# Sch.net
KiCad netlist of a schematic drawn in Altium Designer
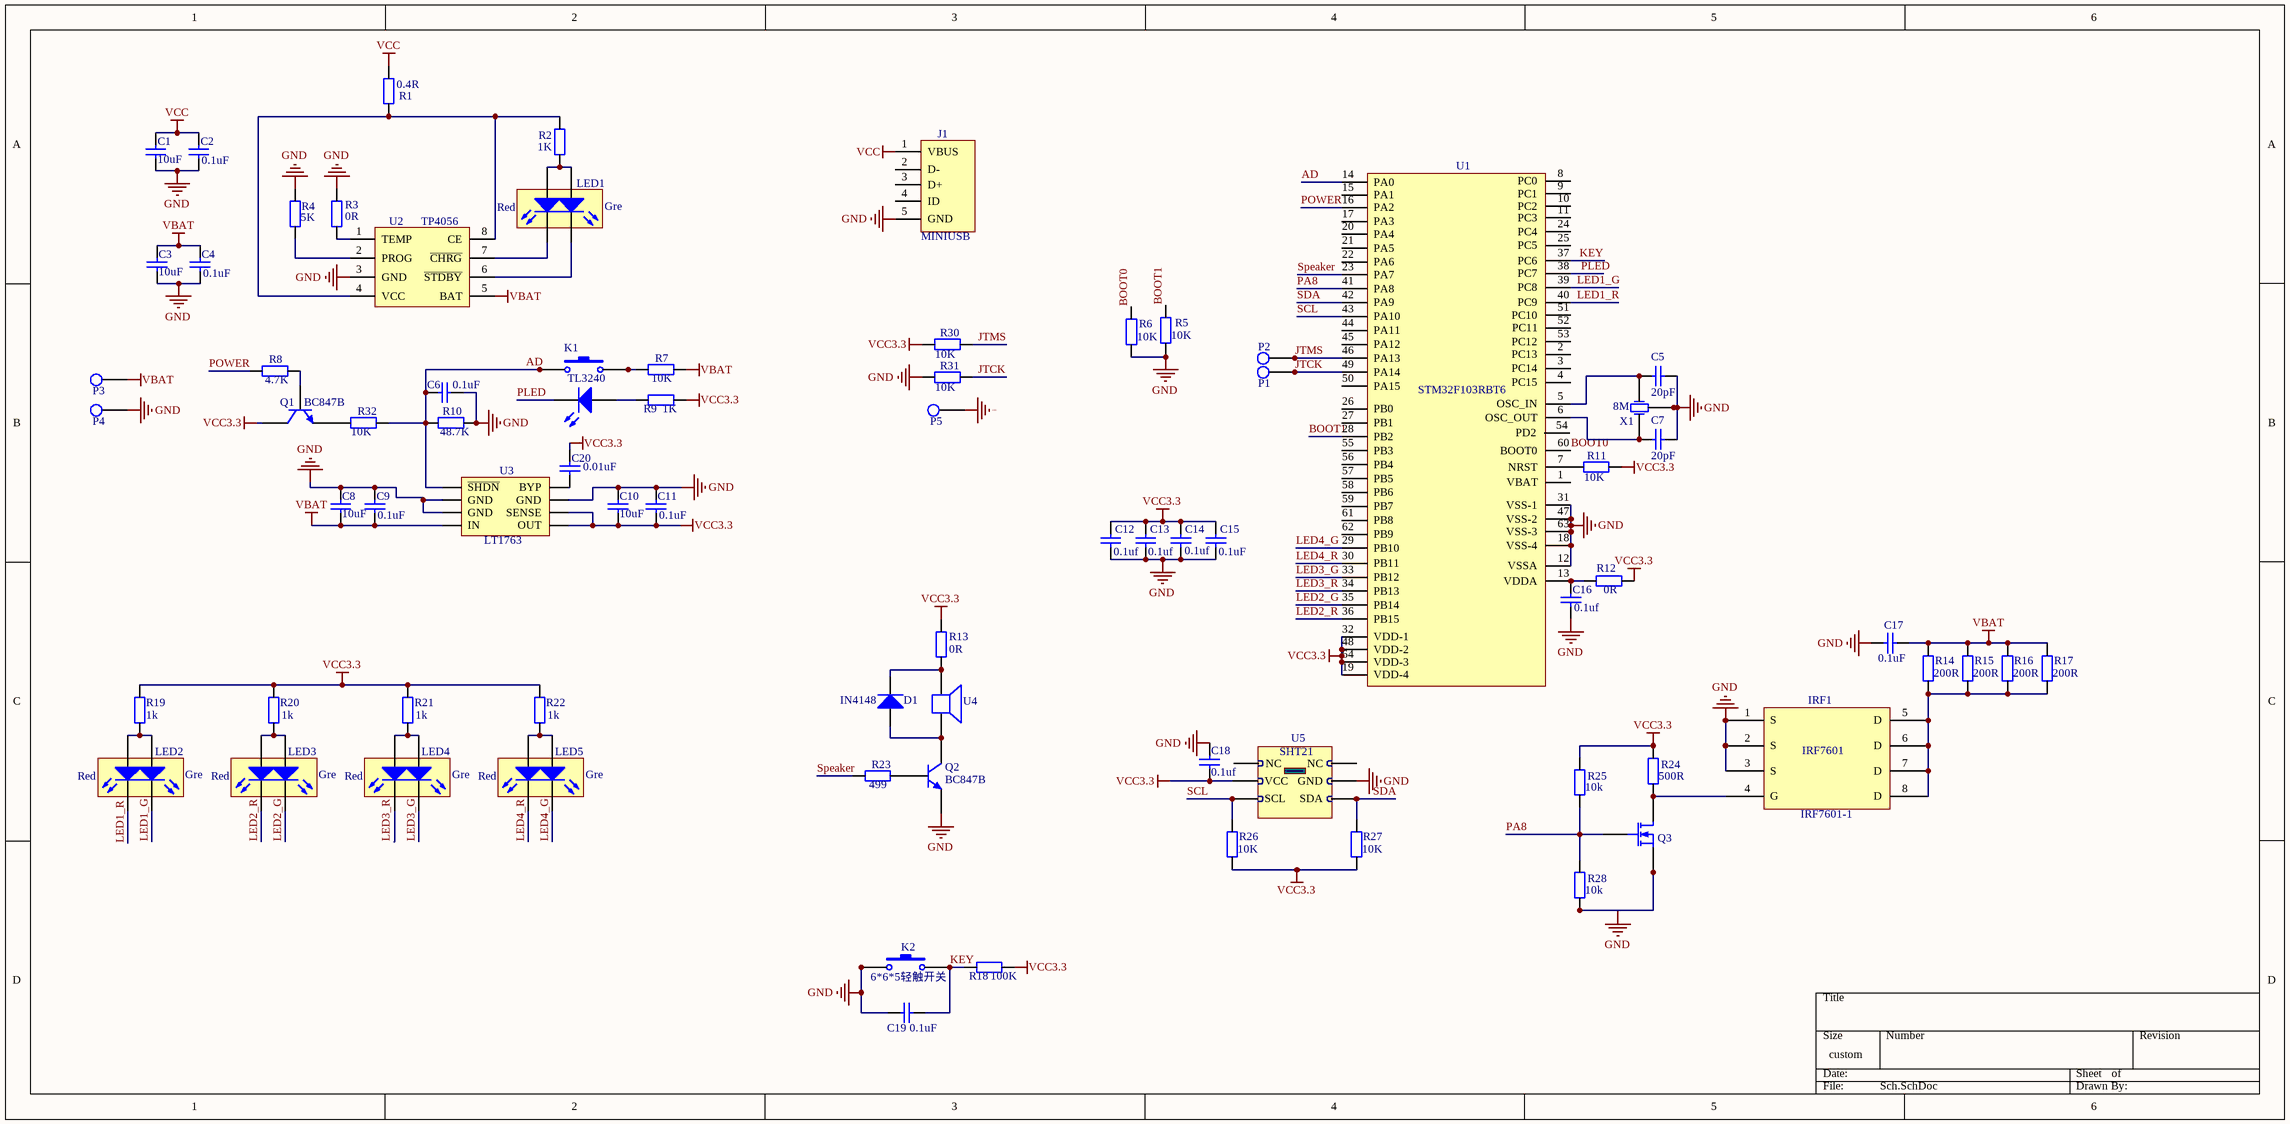
[diagram p0: Sch.SchDoc]

(export (version "E")
  (design (tool "Eeschema 10.0.6"))
  (components
    (comp (ref "C1")
      (value "10uF")
      (footprint "0805")
      (fields (field (name "Comment") "Capacitor-0805"))
      (libsource (lib "原理图库") (part "Capacitor-0805"))
    )
    (comp (ref "C2")
      (value "0.1uF")
      (footprint "0603")
      (fields (field (name "Comment") "Capacitor-0603"))
      (libsource (lib "原理图库") (part "Capacitor-0603"))
    )
    (comp (ref "C3")
      (value "10uF")
      (footprint "0805")
      (fields (field (name "Comment") "Capacitor-0805"))
      (libsource (lib "原理图库") (part "Capacitor-0805"))
    )
    (comp (ref "C4")
      (value "0.1uF")
      (footprint "0603")
      (fields (field (name "Comment") "Capacitor-0603"))
      (libsource (lib "原理图库") (part "Capacitor-0603"))
    )
    (comp (ref "C5")
      (value "20pF")
      (footprint "0603")
      (fields (field (name "Comment") "Capacitor-0805"))
      (libsource (lib "原理图库") (part "Capacitor-0805"))
    )
    (comp (ref "C6")
      (value "0.1uF")
      (footprint "0603")
      (fields (field (name "Comment") "Capacitor-0603"))
      (libsource (lib "原理图库") (part "Capacitor-0603"))
    )
    (comp (ref "C7")
      (value "20pF")
      (footprint "0603")
      (fields (field (name "Comment") "Capacitor-0805"))
      (libsource (lib "原理图库") (part "Capacitor-0805"))
    )
    (comp (ref "C8")
      (value "10uF")
      (footprint "0805")
      (fields (field (name "Comment") "Capacitor-0805"))
      (libsource (lib "原理图库") (part "Capacitor-0805"))
    )
    (comp (ref "C9")
      (value "0.1uF")
      (footprint "0603")
      (fields (field (name "Comment") "Capacitor-0603"))
      (libsource (lib "原理图库") (part "Capacitor-0603"))
    )
    (comp (ref "C10")
      (value "10uF")
      (footprint "0805")
      (fields (field (name "Comment") "Capacitor-0805"))
      (libsource (lib "原理图库") (part "Capacitor-0805"))
    )
    (comp (ref "C11")
      (value "0.1uF")
      (footprint "0603")
      (fields (field (name "Comment") "Capacitor-0603"))
      (libsource (lib "原理图库") (part "Capacitor-0603"))
    )
    (comp (ref "C12")
      (value "0.1uf")
      (footprint "0603")
      (fields (field (name "Comment") "Capacitor-0603"))
      (libsource (lib "原理图库") (part "Capacitor-0603"))
    )
    (comp (ref "C13")
      (value "0.1uf")
      (footprint "0603")
      (fields (field (name "Comment") "Capacitor-0603"))
      (libsource (lib "原理图库") (part "Capacitor-0603"))
    )
    (comp (ref "C14")
      (value "0.1uf")
      (footprint "0603")
      (fields (field (name "Comment") "Capacitor-0603"))
      (libsource (lib "原理图库") (part "Capacitor-0603"))
    )
    (comp (ref "C15")
      (value "0.1uF")
      (footprint "0603")
      (fields (field (name "Comment") "Capacitor-0603"))
      (libsource (lib "原理图库") (part "Capacitor-0603"))
    )
    (comp (ref "C16")
      (value "0.1uf")
      (footprint "0603")
      (fields (field (name "Comment") "Capacitor-0603"))
      (libsource (lib "原理图库") (part "Capacitor-0603"))
    )
    (comp (ref "C17")
      (value "0.1uF")
      (footprint "0603")
      (fields (field (name "Comment") "Capacitor-0603"))
      (libsource (lib "原理图库") (part "Capacitor-0603"))
    )
    (comp (ref "C18")
      (value "0.1uf")
      (footprint "0603")
      (fields (field (name "Comment") "Capacitor-0603"))
      (libsource (lib "原理图库") (part "Capacitor-0603"))
    )
    (comp (ref "C19")
      (value "0.1uF")
      (footprint "0603")
      (fields (field (name "Comment") "Capacitor-0603"))
      (libsource (lib "原理图库") (part "Capacitor-0603"))
    )
    (comp (ref "C20")
      (value "0.01uF")
      (footprint "0603")
      (fields (field (name "Comment") "Capacitor-0805"))
      (libsource (lib "集成库—大岐") (part "Capacitor-0805"))
    )
    (comp (ref "D1")
      (value "IN5824")
      (footprint "IN5824")
      (fields (field (name "ALTIUM_UNNAMED_1") "IN4148"))
      (libsource (lib "集成库—大岐") (part "IN5824"))
    )
    (comp (ref "IRF1")
      (value "IRF7601-1")
      (footprint "IRF7601_Micro")
      (description "IRF7601")
      (libsource (lib "*") (part "Component_1"))
    )
    (comp (ref "J1")
      (value "MINIUSB")
      (footprint "MicoUsb")
      (fields (field (name "NAME") "MINIUSB"))
      (libsource (lib "原理图库") (part "MINIUSB"))
    )
    (comp (ref "K1") (value "TL3240") (footprint "TL3240") (libsource (lib "原理图库") (part "TL3240")))
    (comp (ref "K2")
      (value "6*6*5轻触开关")
      (footprint "四脚轻触开关（6*6*5）")
      (fields (field (name "Comment") "轻触开关"))
      (libsource (lib "原理图库") (part "轻触开关"))
    )
    (comp (ref "LED1")
      (value "LED0603*2")
      (footprint "LED0603*2")
      (libsource (lib "原理图库") (part "LED0603*2"))
    )
    (comp (ref "LED2")
      (value "LED0603*2")
      (footprint "LED0603*2")
      (libsource (lib "原理图库") (part "LED0603*2"))
    )
    (comp (ref "LED3")
      (value "LED0603*2")
      (footprint "LED0603*2")
      (libsource (lib "原理图库") (part "LED0603*2"))
    )
    (comp (ref "LED4")
      (value "LED0603*2")
      (footprint "LED0603*2")
      (libsource (lib "原理图库") (part "LED0603*2"))
    )
    (comp (ref "LED5")
      (value "LED0603*2")
      (footprint "LED0603*2")
      (libsource (lib "原理图库") (part "LED0603*2"))
    )
    (comp (ref "P1") (value "焊盘") (footprint "测点") (libsource (lib "原理图库") (part "焊盘")))
    (comp (ref "P2") (value "焊盘") (footprint "测点") (libsource (lib "原理图库") (part "焊盘")))
    (comp (ref "P3") (value "焊盘") (footprint "测点") (libsource (lib "原理图库") (part "焊盘")))
    (comp (ref "P4") (value "焊盘") (footprint "测点") (libsource (lib "原理图库") (part "焊盘")))
    (comp (ref "P5") (value "焊盘") (footprint "测点") (libsource (lib "原理图库") (part "焊盘")))
    (comp (ref "Q1")
      (value "BC847")
      (footprint "BC847B")
      (fields (field (name "NAME") "BC847B"))
      (libsource (lib "原理图库") (part "BC847"))
    )
    (comp (ref "Q2")
      (value "BC847")
      (footprint "BC847B")
      (fields (field (name "NAME") "BC847B"))
      (libsource (lib "原理图库") (part "BC847"))
    )
    (comp (ref "Q3") (value "MOSFET_N") (footprint "MOSFET_N") (libsource (lib "原理图库") (part "MOSFET_N")))
    (comp (ref "R1")
      (value "0.4R")
      (footprint "0603")
      (fields (field (name "Comment") "Resistor-0603"))
      (libsource (lib "原理图库") (part "Resistor-0603"))
    )
    (comp (ref "R2")
      (value "1K")
      (footprint "0603")
      (fields (field (name "Comment") "Resistor-0603"))
      (libsource (lib "") (part "Resistor-0603_3"))
    )
    (comp (ref "R3")
      (value "0R")
      (footprint "0603")
      (fields (field (name "Comment") "Resistor-0603"))
      (libsource (lib "") (part "Resistor-0603_3"))
    )
    (comp (ref "R4")
      (value "5K")
      (footprint "0603")
      (fields (field (name "Comment") "Resistor-0603"))
      (libsource (lib "") (part "Resistor-0603_3"))
    )
    (comp (ref "R5")
      (value "10K")
      (footprint "0603")
      (fields (field (name "Comment") "Resistor-0603"))
      (libsource (lib "原理图库") (part "Resistor-0603"))
    )
    (comp (ref "R6")
      (value "10K")
      (footprint "0603")
      (fields (field (name "Comment") "Resistor-0603"))
      (libsource (lib "原理图库") (part "Resistor-0603"))
    )
    (comp (ref "R7")
      (value "10K")
      (footprint "0603")
      (fields (field (name "Comment") "Resistor-0603"))
      (libsource (lib "") (part "Resistor-0603_2"))
    )
    (comp (ref "R8")
      (value "4.7K")
      (footprint "0603")
      (fields (field (name "Comment") "Resistor-0603"))
      (libsource (lib "") (part "Resistor-0603_1"))
    )
    (comp (ref "R9")
      (value "1K")
      (footprint "0603")
      (fields (field (name "Comment") "Resistor-0603"))
      (libsource (lib "") (part "Resistor-0603_2"))
    )
    (comp (ref "R10")
      (value "48.7K")
      (footprint "0603")
      (fields (field (name "Comment") "Resistor-0603"))
      (libsource (lib "") (part "Resistor-0603_2"))
    )
    (comp (ref "R11")
      (value "10K")
      (footprint "0603")
      (fields (field (name "Comment") "Resistor-0603"))
      (libsource (lib "") (part "Resistor-0603_1"))
    )
    (comp (ref "R12")
      (value "0R")
      (footprint "0603")
      (fields (field (name "Comment") "Resistor-0603"))
      (libsource (lib "") (part "Resistor-0603_1"))
    )
    (comp (ref "R13")
      (value "0R")
      (footprint "0603")
      (fields (field (name "Comment") "Resistor-0603"))
      (libsource (lib "原理图库") (part "Resistor-0603"))
    )
    (comp (ref "R14")
      (value "200R")
      (footprint "0805")
      (fields (field (name "Comment") "Resistor-0805"))
      (libsource (lib "原理图库") (part "Resistor-0805"))
    )
    (comp (ref "R15")
      (value "200R")
      (footprint "0805")
      (fields (field (name "Comment") "Resistor-0805"))
      (libsource (lib "原理图库") (part "Resistor-0805"))
    )
    (comp (ref "R16")
      (value "200R")
      (footprint "0805")
      (fields (field (name "Comment") "Resistor-0805"))
      (libsource (lib "原理图库") (part "Resistor-0805"))
    )
    (comp (ref "R17")
      (value "200R")
      (footprint "0805")
      (fields (field (name "Comment") "Resistor-0805"))
      (libsource (lib "原理图库") (part "Resistor-0805"))
    )
    (comp (ref "R18")
      (value "100K")
      (footprint "0603")
      (fields (field (name "Comment") "Resistor-0603"))
      (libsource (lib "") (part "Resistor-0603_2"))
    )
    (comp (ref "R19")
      (value "1k")
      (footprint "0603")
      (fields (field (name "Comment") "Resistor-0603"))
      (libsource (lib "原理图库") (part "Resistor-0603"))
    )
    (comp (ref "R20")
      (value "1k")
      (footprint "0603")
      (fields (field (name "Comment") "Resistor-0603"))
      (libsource (lib "原理图库") (part "Resistor-0603"))
    )
    (comp (ref "R21")
      (value "1k")
      (footprint "0603")
      (fields (field (name "Comment") "Resistor-0603"))
      (libsource (lib "原理图库") (part "Resistor-0603"))
    )
    (comp (ref "R22")
      (value "1k")
      (footprint "0603")
      (fields (field (name "Comment") "Resistor-0603"))
      (libsource (lib "原理图库") (part "Resistor-0603"))
    )
    (comp (ref "R23")
      (value "499")
      (footprint "0603")
      (fields (field (name "Comment") "Resistor-0603"))
      (libsource (lib "") (part "Resistor-0603_1"))
    )
    (comp (ref "R24")
      (value "500R")
      (footprint "0603")
      (fields (field (name "Comment") "Resistor-0603"))
      (libsource (lib "原理图库") (part "Resistor-0603"))
    )
    (comp (ref "R25")
      (value "10k")
      (footprint "0603")
      (fields (field (name "Comment") "Resistor-0603"))
      (libsource (lib "原理图库") (part "Resistor-0603"))
    )
    (comp (ref "R26")
      (value "10K")
      (footprint "0603")
      (fields (field (name "Comment") "Resistor-0603"))
      (libsource (lib "原理图库") (part "Resistor-0603"))
    )
    (comp (ref "R27")
      (value "10K")
      (footprint "0603")
      (fields (field (name "Comment") "Resistor-0603"))
      (libsource (lib "原理图库") (part "Resistor-0603"))
    )
    (comp (ref "R28")
      (value "10k")
      (footprint "0603")
      (fields (field (name "Comment") "Resistor-0603"))
      (libsource (lib "原理图库") (part "Resistor-0603"))
    )
    (comp (ref "R30")
      (value "10K")
      (footprint "0603")
      (fields (field (name "Comment") "Resistor-0603"))
      (libsource (lib "") (part "Resistor-0603_1"))
    )
    (comp (ref "R31")
      (value "10K")
      (footprint "0603")
      (fields (field (name "Comment") "Resistor-0603"))
      (libsource (lib "") (part "Resistor-0603_1"))
    )
    (comp (ref "R32")
      (value "10K")
      (footprint "0603")
      (fields (field (name "Comment") "Resistor-0603"))
      (libsource (lib "") (part "Resistor-0603_1"))
    )
    (comp (ref "U1")
      (value "STM32F103RBT6")
      (footprint "STM32F103RBT6")
      (fields (field (name "NAME") "STM32F103RBT6"))
      (libsource (lib "原理图库") (part "STM32F103RBT6"))
    )
    (comp (ref "U2") (value "TP4056") (footprint "TP4056") (libsource (lib "原理图库") (part "TP4056")))
    (comp (ref "U3") (value "LT1763") (footprint "LT1963") (libsource (lib "原理图库") (part "LT1763")))
    (comp (ref "U4")
      (value "Speaker")
      (footprint "Speaker（5*5*2.0）")
      (libsource (lib "原理图库") (part "Speaker"))
    )
    (comp (ref "U5")
      (value "SHIT21")
      (footprint "SHT21")
      (fields (field (name "NAME") "SHT21"))
      (libsource (lib "原理图库") (part "SHIT21"))
    )
    (comp (ref "X1")
      (value "8M")
      (footprint "3225无源晶振")
      (fields (field (name "Comment") "3225无源晶振"))
      (libsource (lib "原理图库") (part "3225无源晶振"))
    )
  )
  (nets
    (net (code "1") (name "/AD") (class "Default")
      (node (ref "C6") (pin "2") (pinfunction "2_2") (pintype "passive"))
      (node (ref "K1") (pin "1") (pinfunction "1_1") (pintype "passive"))
      (node (ref "K1") (pin "2") (pinfunction "2_2") (pintype "passive"))
      (node (ref "R10") (pin "1") (pinfunction "1_1") (pintype "passive"))
      (node (ref "R32") (pin "1") (pinfunction "1_1") (pintype "passive"))
      (node (ref "U1") (pin "14") (pinfunction "PA0_14") (pintype "passive"))
      (node (ref "U3") (pin "5") (pinfunction "~{SHDN}_5") (pintype "passive"))
    )
    (net (code "2") (name "/BOOT0") (class "Default")
      (node (ref "R6") (pin "2") (pinfunction "2_2") (pintype "passive"))
      (node (ref "U1") (pin "60") (pinfunction "BOOT0_60") (pintype "passive"))
    )
    (net (code "3") (name "/BOOT1") (class "Default")
      (node (ref "R5") (pin "2") (pinfunction "2_2") (pintype "passive"))
      (node (ref "U1") (pin "28") (pinfunction "PB2_28") (pintype "passive"))
    )
    (net (code "4") (name "/JTCK") (class "Default")
      (node (ref "P1") (pin "1") (pinfunction "1_1") (pintype "passive"))
      (node (ref "R31") (pin "1") (pinfunction "1_1") (pintype "passive"))
      (node (ref "U1") (pin "49") (pinfunction "PA14_49") (pintype "passive"))
    )
    (net (code "5") (name "/JTMS") (class "Default")
      (node (ref "P2") (pin "1") (pinfunction "1_1") (pintype "passive"))
      (node (ref "R30") (pin "1") (pinfunction "1_1") (pintype "passive"))
      (node (ref "U1") (pin "46") (pinfunction "PA13_46") (pintype "passive"))
    )
    (net (code "6") (name "/KEY") (class "Default")
      (node (ref "C19") (pin "1") (pinfunction "1_1") (pintype "passive"))
      (node (ref "K2") (pin "3") (pinfunction "3_3") (pintype "passive"))
      (node (ref "K2") (pin "4") (pinfunction "4_4") (pintype "passive"))
      (node (ref "R18") (pin "1") (pinfunction "1_1") (pintype "passive"))
      (node (ref "U1") (pin "37") (pinfunction "PC6_37") (pintype "passive"))
    )
    (net (code "7") (name "/LED1_G") (class "Default")
      (node (ref "LED2") (pin "3") (pinfunction "2_3") (pintype "passive"))
      (node (ref "U1") (pin "39") (pinfunction "PC8_39") (pintype "passive"))
    )
    (net (code "8") (name "/LED1_R") (class "Default")
      (node (ref "LED2") (pin "4") (pinfunction "2_4") (pintype "passive"))
      (node (ref "U1") (pin "40") (pinfunction "PC9_40") (pintype "passive"))
    )
    (net (code "9") (name "/LED2_G") (class "Default")
      (node (ref "LED3") (pin "3") (pinfunction "2_3") (pintype "passive"))
      (node (ref "U1") (pin "35") (pinfunction "PB14_35") (pintype "passive"))
    )
    (net (code "10") (name "/LED2_R") (class "Default")
      (node (ref "LED3") (pin "4") (pinfunction "2_4") (pintype "passive"))
      (node (ref "U1") (pin "36") (pinfunction "PB15_36") (pintype "passive"))
    )
    (net (code "11") (name "/LED3_G") (class "Default")
      (node (ref "LED4") (pin "3") (pinfunction "2_3") (pintype "passive"))
      (node (ref "U1") (pin "33") (pinfunction "PB12_33") (pintype "passive"))
    )
    (net (code "12") (name "/LED3_R") (class "Default")
      (node (ref "LED4") (pin "4") (pinfunction "2_4") (pintype "passive"))
      (node (ref "U1") (pin "34") (pinfunction "PB13_34") (pintype "passive"))
    )
    (net (code "13") (name "/LED4_G") (class "Default")
      (node (ref "LED5") (pin "3") (pinfunction "2_3") (pintype "passive"))
      (node (ref "U1") (pin "29") (pinfunction "PB10_29") (pintype "passive"))
    )
    (net (code "14") (name "/LED4_R") (class "Default")
      (node (ref "LED5") (pin "4") (pinfunction "2_4") (pintype "passive"))
      (node (ref "U1") (pin "30") (pinfunction "PB11_30") (pintype "passive"))
    )
    (net (code "15") (name "/PA8") (class "Default")
      (node (ref "Q3") (pin "1") (pinfunction "G_1") (pintype "passive"))
      (node (ref "R25") (pin "1") (pinfunction "1_1") (pintype "passive"))
      (node (ref "R28") (pin "2") (pinfunction "2_2") (pintype "passive"))
      (node (ref "U1") (pin "41") (pinfunction "PA8_41") (pintype "passive"))
    )
    (net (code "16") (name "/PLED") (class "Default")
      (node (ref "K1") (pin "5") (pinfunction "5_5") (pintype "passive"))
      (node (ref "U1") (pin "38") (pinfunction "PC7_38") (pintype "passive"))
    )
    (net (code "17") (name "/POWER") (class "Default")
      (node (ref "R8") (pin "2") (pinfunction "2_2") (pintype "passive"))
      (node (ref "U1") (pin "16") (pinfunction "PA2_16") (pintype "passive"))
    )
    (net (code "18") (name "/SCL") (class "Default")
      (node (ref "R26") (pin "2") (pinfunction "2_2") (pintype "passive"))
      (node (ref "U1") (pin "43") (pinfunction "PA10_43") (pintype "passive"))
      (node (ref "U5") (pin "5") (pinfunction "SCL_5") (pintype "passive"))
    )
    (net (code "19") (name "/SDA") (class "Default")
      (node (ref "R27") (pin "2") (pinfunction "2_2") (pintype "passive"))
      (node (ref "U1") (pin "42") (pinfunction "PA9_42") (pintype "passive"))
      (node (ref "U5") (pin "6") (pinfunction "SDA_6") (pintype "passive"))
    )
    (net (code "20") (name "/Speaker") (class "Default")
      (node (ref "R23") (pin "2") (pinfunction "2_2") (pintype "passive"))
      (node (ref "U1") (pin "23") (pinfunction "PA7_23") (pintype "passive"))
    )
    (net (code "21") (name "GND") (class "Default")
      (node (ref "C1") (pin "2") (pinfunction "2_2") (pintype "passive"))
      (node (ref "C10") (pin "1") (pinfunction "1_1") (pintype "passive"))
      (node (ref "C11") (pin "2") (pinfunction "2_2") (pintype "passive"))
      (node (ref "C12") (pin "1") (pinfunction "1_1") (pintype "passive"))
      (node (ref "C13") (pin "1") (pinfunction "1_1") (pintype "passive"))
      (node (ref "C14") (pin "1") (pinfunction "1_1") (pintype "passive"))
      (node (ref "C15") (pin "1") (pinfunction "1_1") (pintype "passive"))
      (node (ref "C16") (pin "1") (pinfunction "1_1") (pintype "passive"))
      (node (ref "C17") (pin "2") (pinfunction "2_2") (pintype "passive"))
      (node (ref "C18") (pin "2") (pinfunction "2_2") (pintype "passive"))
      (node (ref "C19") (pin "2") (pinfunction "2_2") (pintype "passive"))
      (node (ref "C2") (pin "1") (pinfunction "1_1") (pintype "passive"))
      (node (ref "C3") (pin "2") (pinfunction "2_2") (pintype "passive"))
      (node (ref "C4") (pin "1") (pinfunction "1_1") (pintype "passive"))
      (node (ref "C5") (pin "1") (pinfunction "1_1") (pintype "passive"))
      (node (ref "C6") (pin "1") (pinfunction "1_1") (pintype "passive"))
      (node (ref "C7") (pin "1") (pinfunction "1_1") (pintype "passive"))
      (node (ref "C8") (pin "1") (pinfunction "1_1") (pintype "passive"))
      (node (ref "C9") (pin "2") (pinfunction "2_2") (pintype "passive"))
      (node (ref "IRF1") (pin "1") (pinfunction "S_1") (pintype "power_in"))
      (node (ref "IRF1") (pin "2") (pinfunction "S_2") (pintype "power_in"))
      (node (ref "IRF1") (pin "3") (pinfunction "S_3") (pintype "power_in"))
      (node (ref "J1") (pin "5") (pinfunction "GND_5") (pintype "passive"))
      (node (ref "K2") (pin "1") (pinfunction "1_1") (pintype "passive"))
      (node (ref "K2") (pin "2") (pinfunction "2_2") (pintype "passive"))
      (node (ref "P4") (pin "1") (pinfunction "1_1") (pintype "passive"))
      (node (ref "P5") (pin "1") (pinfunction "1_1") (pintype "passive"))
      (node (ref "Q2") (pin "1") (pinfunction "E_1") (pintype "passive"))
      (node (ref "R10") (pin "2") (pinfunction "2_2") (pintype "passive"))
      (node (ref "R3") (pin "1") (pinfunction "1_1") (pintype "passive"))
      (node (ref "R31") (pin "2") (pinfunction "2_2") (pintype "passive"))
      (node (ref "R4") (pin "1") (pinfunction "1_1") (pintype "passive"))
      (node (ref "R5") (pin "1") (pinfunction "1_1") (pintype "passive"))
      (node (ref "R6") (pin "1") (pinfunction "1_1") (pintype "passive"))
      (node (ref "U1") (pin "12") (pinfunction "VSSA_12") (pintype "passive"))
      (node (ref "U1") (pin "18") (pinfunction "VSS-4_18") (pintype "passive"))
      (node (ref "U1") (pin "31") (pinfunction "VSS-1_31") (pintype "passive"))
      (node (ref "U1") (pin "47") (pinfunction "VSS-2_47") (pintype "passive"))
      (node (ref "U1") (pin "63") (pinfunction "VSS-3_63") (pintype "passive"))
      (node (ref "U2") (pin "3") (pinfunction "GND_3") (pintype "passive"))
      (node (ref "U3") (pin "3") (pinfunction "GND_3") (pintype "passive"))
      (node (ref "U3") (pin "6") (pinfunction "GND_6") (pintype "passive"))
      (node (ref "U3") (pin "7") (pinfunction "GND_7") (pintype "passive"))
      (node (ref "U5") (pin "4") (pinfunction "GND_4") (pintype "passive"))
      (node (ref "X1") (pin "2") (pinfunction "GND_2") (pintype "passive"))
      (node (ref "X1") (pin "4") (pinfunction "GND_4") (pintype "passive"))
    )
    (net (code "22") (name "Net-(D1-A)") (class "Default")
      (node (ref "D1") (pin "1") (pinfunction "A_1") (pintype "passive"))
      (node (ref "Q2") (pin "3") (pinfunction "C_3") (pintype "passive"))
      (node (ref "U4") (pin "1") (pinfunction "1_1") (pintype "passive"))
    )
    (net (code "23") (name "Net-(D1-K)") (class "Default")
      (node (ref "D1") (pin "2") (pinfunction "K_2") (pintype "passive"))
      (node (ref "R13") (pin "1") (pinfunction "1_1") (pintype "passive"))
      (node (ref "U4") (pin "2") (pinfunction "2_2") (pintype "passive"))
    )
    (net (code "24") (name "Net-(IRF1-D-Pad5)") (class "Default")
      (node (ref "IRF1") (pin "5") (pinfunction "D_5") (pintype "power_in"))
      (node (ref "IRF1") (pin "6") (pinfunction "D_6") (pintype "power_in"))
      (node (ref "IRF1") (pin "7") (pinfunction "D_7") (pintype "power_in"))
      (node (ref "IRF1") (pin "8") (pinfunction "D_8") (pintype "power_in"))
      (node (ref "R14") (pin "1") (pinfunction "1_1") (pintype "passive"))
      (node (ref "R15") (pin "1") (pinfunction "1_1") (pintype "passive"))
      (node (ref "R16") (pin "1") (pinfunction "1_1") (pintype "passive"))
      (node (ref "R17") (pin "1") (pinfunction "1_1") (pintype "passive"))
    )
    (net (code "25") (name "Net-(IRF1-G)") (class "Default")
      (node (ref "IRF1") (pin "4") (pinfunction "G_4") (pintype "power_in"))
      (node (ref "Q3") (pin "3") (pinfunction "D_3") (pintype "passive"))
      (node (ref "R24") (pin "1") (pinfunction "1_1") (pintype "passive"))
    )
    (net (code "26") (name "Net-(K1-A)") (class "Default")
      (node (ref "K1") (pin "6") (pinfunction "A_6") (pintype "passive"))
      (node (ref "R9") (pin "1") (pinfunction "1_1") (pintype "passive"))
    )
    (net (code "27") (name "Net-(K1-Pad3)") (class "Default")
      (node (ref "K1") (pin "3") (pinfunction "3_3") (pintype "passive"))
      (node (ref "K1") (pin "4") (pinfunction "4_4") (pintype "passive"))
      (node (ref "R7") (pin "1") (pinfunction "1_1") (pintype "passive"))
    )
    (net (code "28") (name "Net-(LED1-A-Pad1)") (class "Default")
      (node (ref "LED1") (pin "1") (pinfunction "A_1") (pintype "passive"))
      (node (ref "LED1") (pin "2") (pinfunction "A_2") (pintype "passive"))
      (node (ref "R2") (pin "2") (pinfunction "2_2") (pintype "passive"))
    )
    (net (code "29") (name "Net-(LED2-A-Pad1)") (class "Default")
      (node (ref "LED2") (pin "1") (pinfunction "A_1") (pintype "passive"))
      (node (ref "LED2") (pin "2") (pinfunction "A_2") (pintype "passive"))
      (node (ref "R19") (pin "1") (pinfunction "1_1") (pintype "passive"))
    )
    (net (code "30") (name "Net-(LED3-A-Pad1)") (class "Default")
      (node (ref "LED3") (pin "1") (pinfunction "A_1") (pintype "passive"))
      (node (ref "LED3") (pin "2") (pinfunction "A_2") (pintype "passive"))
      (node (ref "R20") (pin "1") (pinfunction "1_1") (pintype "passive"))
    )
    (net (code "31") (name "Net-(LED4-A-Pad1)") (class "Default")
      (node (ref "LED4") (pin "1") (pinfunction "A_1") (pintype "passive"))
      (node (ref "LED4") (pin "2") (pinfunction "A_2") (pintype "passive"))
      (node (ref "R21") (pin "1") (pinfunction "1_1") (pintype "passive"))
    )
    (net (code "32") (name "Net-(LED5-A-Pad1)") (class "Default")
      (node (ref "LED5") (pin "1") (pinfunction "A_1") (pintype "passive"))
      (node (ref "LED5") (pin "2") (pinfunction "A_2") (pintype "passive"))
      (node (ref "R22") (pin "1") (pinfunction "1_1") (pintype "passive"))
    )
    (net (code "33") (name "Net-(Q1-B)") (class "Default")
      (node (ref "Q1") (pin "2") (pinfunction "B_2") (pintype "passive"))
      (node (ref "R8") (pin "1") (pinfunction "1_1") (pintype "passive"))
    )
    (net (code "34") (name "Net-(Q1-E)") (class "Default")
      (node (ref "Q1") (pin "1") (pinfunction "E_1") (pintype "passive"))
      (node (ref "R32") (pin "2") (pinfunction "2_2") (pintype "passive"))
    )
    (net (code "35") (name "Net-(Q2-B)") (class "Default")
      (node (ref "Q2") (pin "2") (pinfunction "B_2") (pintype "passive"))
      (node (ref "R23") (pin "1") (pinfunction "1_1") (pintype "passive"))
    )
    (net (code "36") (name "Net-(Q3-S)") (class "Default")
      (node (ref "Q3") (pin "2") (pinfunction "S_2") (pintype "passive"))
      (node (ref "R28") (pin "1") (pinfunction "1_1") (pintype "passive"))
    )
    (net (code "37") (name "Net-(U1-NRST)") (class "Default")
      (node (ref "R11") (pin "2") (pinfunction "2_2") (pintype "passive"))
      (node (ref "U1") (pin "7") (pinfunction "NRST_7") (pintype "passive"))
    )
    (net (code "38") (name "Net-(U1-OSC_IN)") (class "Default")
      (node (ref "C5") (pin "2") (pinfunction "2_2") (pintype "passive"))
      (node (ref "U1") (pin "5") (pinfunction "OSC_IN_5") (pintype "passive"))
      (node (ref "X1") (pin "3") (pinfunction "OSC2_3") (pintype "passive"))
    )
    (net (code "39") (name "Net-(U1-OSC_OUT)") (class "Default")
      (node (ref "C7") (pin "2") (pinfunction "2_2") (pintype "passive"))
      (node (ref "U1") (pin "6") (pinfunction "OSC_OUT_6") (pintype "passive"))
      (node (ref "X1") (pin "1") (pinfunction "OSC1_1") (pintype "passive"))
    )
    (net (code "40") (name "Net-(U1-VDDA)") (class "Default")
      (node (ref "C16") (pin "2") (pinfunction "2_2") (pintype "passive"))
      (node (ref "R12") (pin "2") (pinfunction "2_2") (pintype "passive"))
      (node (ref "U1") (pin "13") (pinfunction "VDDA_13") (pintype "passive"))
    )
    (net (code "41") (name "Net-(U2-CE)") (class "Default")
      (node (ref "R1") (pin "1") (pinfunction "1_1") (pintype "passive"))
      (node (ref "R2") (pin "1") (pinfunction "1_1") (pintype "passive"))
      (node (ref "U2") (pin "4") (pinfunction "VCC_4") (pintype "passive"))
      (node (ref "U2") (pin "8") (pinfunction "CE_8") (pintype "passive"))
    )
    (net (code "42") (name "Net-(U2-PROG)") (class "Default")
      (node (ref "R4") (pin "2") (pinfunction "2_2") (pintype "passive"))
      (node (ref "U2") (pin "2") (pinfunction "PROG_2") (pintype "passive"))
    )
    (net (code "43") (name "Net-(U2-TEMP)") (class "Default")
      (node (ref "R3") (pin "2") (pinfunction "2_2") (pintype "passive"))
      (node (ref "U2") (pin "1") (pinfunction "TEMP_1") (pintype "passive"))
    )
    (net (code "44") (name "Net-(U2-~{CHRG})") (class "Default")
      (node (ref "LED1") (pin "4") (pinfunction "2_4") (pintype "passive"))
      (node (ref "U2") (pin "7") (pinfunction "~{CHRG}_7") (pintype "passive"))
    )
    (net (code "45") (name "Net-(U2-~{STDBY})") (class "Default")
      (node (ref "LED1") (pin "3") (pinfunction "2_3") (pintype "passive"))
      (node (ref "U2") (pin "6") (pinfunction "~{STDBY}_6") (pintype "passive"))
    )
    (net (code "46") (name "Net-(U3-BYP)") (class "Default")
      (node (ref "C20") (pin "1") (pinfunction "1_1") (pintype "passive"))
      (node (ref "U3") (pin "4") (pinfunction "BYP_4") (pintype "passive"))
    )
    (net (code "47") (name "VBAT") (class "Default")
      (node (ref "C17") (pin "1") (pinfunction "1_1") (pintype "passive"))
      (node (ref "C3") (pin "1") (pinfunction "1_1") (pintype "passive"))
      (node (ref "C4") (pin "2") (pinfunction "2_2") (pintype "passive"))
      (node (ref "C8") (pin "2") (pinfunction "2_2") (pintype "passive"))
      (node (ref "C9") (pin "1") (pinfunction "1_1") (pintype "passive"))
      (node (ref "P3") (pin "1") (pinfunction "1_1") (pintype "passive"))
      (node (ref "R14") (pin "2") (pinfunction "2_2") (pintype "passive"))
      (node (ref "R15") (pin "2") (pinfunction "2_2") (pintype "passive"))
      (node (ref "R16") (pin "2") (pinfunction "2_2") (pintype "passive"))
      (node (ref "R17") (pin "2") (pinfunction "2_2") (pintype "passive"))
      (node (ref "R7") (pin "2") (pinfunction "2_2") (pintype "passive"))
      (node (ref "U2") (pin "5") (pinfunction "BAT_5") (pintype "passive"))
      (node (ref "U3") (pin "8") (pinfunction "IN_8") (pintype "passive"))
    )
    (net (code "48") (name "VCC") (class "Default")
      (node (ref "C1") (pin "1") (pinfunction "1_1") (pintype "passive"))
      (node (ref "C2") (pin "2") (pinfunction "2_2") (pintype "passive"))
      (node (ref "J1") (pin "1") (pinfunction "VBUS_1") (pintype "passive"))
      (node (ref "R1") (pin "2") (pinfunction "2_2") (pintype "passive"))
    )
    (net (code "49") (name "VCC3.3") (class "Default")
      (node (ref "C10") (pin "2") (pinfunction "2_2") (pintype "passive"))
      (node (ref "C11") (pin "1") (pinfunction "1_1") (pintype "passive"))
      (node (ref "C12") (pin "2") (pinfunction "2_2") (pintype "passive"))
      (node (ref "C13") (pin "2") (pinfunction "2_2") (pintype "passive"))
      (node (ref "C14") (pin "2") (pinfunction "2_2") (pintype "passive"))
      (node (ref "C15") (pin "2") (pinfunction "2_2") (pintype "passive"))
      (node (ref "C18") (pin "1") (pinfunction "1_1") (pintype "passive"))
      (node (ref "C20") (pin "2") (pinfunction "2_2") (pintype "passive"))
      (node (ref "Q1") (pin "3") (pinfunction "C_3") (pintype "passive"))
      (node (ref "R11") (pin "1") (pinfunction "1_1") (pintype "passive"))
      (node (ref "R12") (pin "1") (pinfunction "1_1") (pintype "passive"))
      (node (ref "R13") (pin "2") (pinfunction "2_2") (pintype "passive"))
      (node (ref "R18") (pin "2") (pinfunction "2_2") (pintype "passive"))
      (node (ref "R19") (pin "2") (pinfunction "2_2") (pintype "passive"))
      (node (ref "R20") (pin "2") (pinfunction "2_2") (pintype "passive"))
      (node (ref "R21") (pin "2") (pinfunction "2_2") (pintype "passive"))
      (node (ref "R22") (pin "2") (pinfunction "2_2") (pintype "passive"))
      (node (ref "R24") (pin "2") (pinfunction "2_2") (pintype "passive"))
      (node (ref "R25") (pin "2") (pinfunction "2_2") (pintype "passive"))
      (node (ref "R26") (pin "1") (pinfunction "1_1") (pintype "passive"))
      (node (ref "R27") (pin "1") (pinfunction "1_1") (pintype "passive"))
      (node (ref "R30") (pin "2") (pinfunction "2_2") (pintype "passive"))
      (node (ref "R9") (pin "2") (pinfunction "2_2") (pintype "passive"))
      (node (ref "U1") (pin "19") (pinfunction "VDD-4_19") (pintype "passive"))
      (node (ref "U1") (pin "32") (pinfunction "VDD-1_32") (pintype "passive"))
      (node (ref "U1") (pin "48") (pinfunction "VDD-2_48") (pintype "passive"))
      (node (ref "U1") (pin "64") (pinfunction "VDD-3_64") (pintype "passive"))
      (node (ref "U3") (pin "1") (pinfunction "OUT_1") (pintype "passive"))
      (node (ref "U3") (pin "2") (pinfunction "SENSE_2") (pintype "passive"))
      (node (ref "U5") (pin "3") (pinfunction "VCC_3") (pintype "passive"))
    )
    (net (code "50") (name "unconnected-(J1-D+-Pad3)") (class "Default")
      (node (ref "J1") (pin "3") (pinfunction "D+_3") (pintype "passive"))
    )
    (net (code "51") (name "unconnected-(J1-D--Pad2)") (class "Default")
      (node (ref "J1") (pin "2") (pinfunction "D-_2") (pintype "passive"))
    )
    (net (code "52") (name "unconnected-(J1-ID-Pad4)") (class "Default")
      (node (ref "J1") (pin "4") (pinfunction "ID_4") (pintype "passive"))
    )
    (net (code "53") (name "unconnected-(J1-Pad6)") (class "Default")
      (node (ref "J1") (pin "6") (pinfunction "6_6") (pintype "passive"))
    )
    (net (code "54") (name "unconnected-(J1-Pad7)") (class "Default")
      (node (ref "J1") (pin "7") (pinfunction "7_7") (pintype "passive"))
    )
    (net (code "55") (name "unconnected-(J1-Pad8)") (class "Default")
      (node (ref "J1") (pin "8") (pinfunction "8_8") (pintype "passive"))
    )
    (net (code "56") (name "unconnected-(J1-Pad9)") (class "Default")
      (node (ref "J1") (pin "9") (pinfunction "9_9") (pintype "passive"))
    )
    (net (code "57") (name "unconnected-(U1-PA1-Pad15)") (class "Default")
      (node (ref "U1") (pin "15") (pinfunction "PA1_15") (pintype "passive"))
    )
    (net (code "58") (name "unconnected-(U1-PA3-Pad17)") (class "Default")
      (node (ref "U1") (pin "17") (pinfunction "PA3_17") (pintype "passive"))
    )
    (net (code "59") (name "unconnected-(U1-PA4-Pad20)") (class "Default")
      (node (ref "U1") (pin "20") (pinfunction "PA4_20") (pintype "passive"))
    )
    (net (code "60") (name "unconnected-(U1-PA5-Pad21)") (class "Default")
      (node (ref "U1") (pin "21") (pinfunction "PA5_21") (pintype "passive"))
    )
    (net (code "61") (name "unconnected-(U1-PA6-Pad22)") (class "Default")
      (node (ref "U1") (pin "22") (pinfunction "PA6_22") (pintype "passive"))
    )
    (net (code "62") (name "unconnected-(U1-PA11-Pad44)") (class "Default")
      (node (ref "U1") (pin "44") (pinfunction "PA11_44") (pintype "passive"))
    )
    (net (code "63") (name "unconnected-(U1-PA12-Pad45)") (class "Default")
      (node (ref "U1") (pin "45") (pinfunction "PA12_45") (pintype "passive"))
    )
    (net (code "64") (name "unconnected-(U1-PA15-Pad50)") (class "Default")
      (node (ref "U1") (pin "50") (pinfunction "PA15_50") (pintype "passive"))
    )
    (net (code "65") (name "unconnected-(U1-PB0-Pad26)") (class "Default")
      (node (ref "U1") (pin "26") (pinfunction "PB0_26") (pintype "passive"))
    )
    (net (code "66") (name "unconnected-(U1-PB1-Pad27)") (class "Default")
      (node (ref "U1") (pin "27") (pinfunction "PB1_27") (pintype "passive"))
    )
    (net (code "67") (name "unconnected-(U1-PB3-Pad55)") (class "Default")
      (node (ref "U1") (pin "55") (pinfunction "PB3_55") (pintype "passive"))
    )
    (net (code "68") (name "unconnected-(U1-PB4-Pad56)") (class "Default")
      (node (ref "U1") (pin "56") (pinfunction "PB4_56") (pintype "passive"))
    )
    (net (code "69") (name "unconnected-(U1-PB5-Pad57)") (class "Default")
      (node (ref "U1") (pin "57") (pinfunction "PB5_57") (pintype "passive"))
    )
    (net (code "70") (name "unconnected-(U1-PB6-Pad58)") (class "Default")
      (node (ref "U1") (pin "58") (pinfunction "PB6_58") (pintype "passive"))
    )
    (net (code "71") (name "unconnected-(U1-PB7-Pad59)") (class "Default")
      (node (ref "U1") (pin "59") (pinfunction "PB7_59") (pintype "passive"))
    )
    (net (code "72") (name "unconnected-(U1-PB8-Pad61)") (class "Default")
      (node (ref "U1") (pin "61") (pinfunction "PB8_61") (pintype "passive"))
    )
    (net (code "73") (name "unconnected-(U1-PB9-Pad62)") (class "Default")
      (node (ref "U1") (pin "62") (pinfunction "PB9_62") (pintype "passive"))
    )
    (net (code "74") (name "unconnected-(U1-PC0-Pad8)") (class "Default")
      (node (ref "U1") (pin "8") (pinfunction "PC0_8") (pintype "passive"))
    )
    (net (code "75") (name "unconnected-(U1-PC1-Pad9)") (class "Default")
      (node (ref "U1") (pin "9") (pinfunction "PC1_9") (pintype "passive"))
    )
    (net (code "76") (name "unconnected-(U1-PC2-Pad10)") (class "Default")
      (node (ref "U1") (pin "10") (pinfunction "PC2_10") (pintype "passive"))
    )
    (net (code "77") (name "unconnected-(U1-PC3-Pad11)") (class "Default")
      (node (ref "U1") (pin "11") (pinfunction "PC3_11") (pintype "passive"))
    )
    (net (code "78") (name "unconnected-(U1-PC4-Pad24)") (class "Default")
      (node (ref "U1") (pin "24") (pinfunction "PC4_24") (pintype "passive"))
    )
    (net (code "79") (name "unconnected-(U1-PC5-Pad25)") (class "Default")
      (node (ref "U1") (pin "25") (pinfunction "PC5_25") (pintype "passive"))
    )
    (net (code "80") (name "unconnected-(U1-PC10-Pad51)") (class "Default")
      (node (ref "U1") (pin "51") (pinfunction "PC10_51") (pintype "passive"))
    )
    (net (code "81") (name "unconnected-(U1-PC11-Pad52)") (class "Default")
      (node (ref "U1") (pin "52") (pinfunction "PC11_52") (pintype "passive"))
    )
    (net (code "82") (name "unconnected-(U1-PC12-Pad53)") (class "Default")
      (node (ref "U1") (pin "53") (pinfunction "PC12_53") (pintype "passive"))
    )
    (net (code "83") (name "unconnected-(U1-PC13-Pad2)") (class "Default")
      (node (ref "U1") (pin "2") (pinfunction "PC13_2") (pintype "passive"))
    )
    (net (code "84") (name "unconnected-(U1-PC14-Pad3)") (class "Default")
      (node (ref "U1") (pin "3") (pinfunction "PC14_3") (pintype "passive"))
    )
    (net (code "85") (name "unconnected-(U1-PC15-Pad4)") (class "Default")
      (node (ref "U1") (pin "4") (pinfunction "PC15_4") (pintype "passive"))
    )
    (net (code "86") (name "unconnected-(U1-PD2-Pad54)") (class "Default")
      (node (ref "U1") (pin "54") (pinfunction "PD2_54") (pintype "passive"))
    )
    (net (code "87") (name "unconnected-(U1-VBAT-Pad1)") (class "Default")
      (node (ref "U1") (pin "1") (pinfunction "VBAT_1") (pintype "passive"))
    )
    (net (code "88") (name "unconnected-(U5-NC-Pad1)") (class "Default")
      (node (ref "U5") (pin "1") (pinfunction "NC_1") (pintype "passive"))
    )
    (net (code "89") (name "unconnected-(U5-NC-Pad2)") (class "Default")
      (node (ref "U5") (pin "2") (pinfunction "NC_2") (pintype "passive"))
    )
  )
)
